# Leah_board.net
KiCad netlist of a schematic drawn in EAGLE
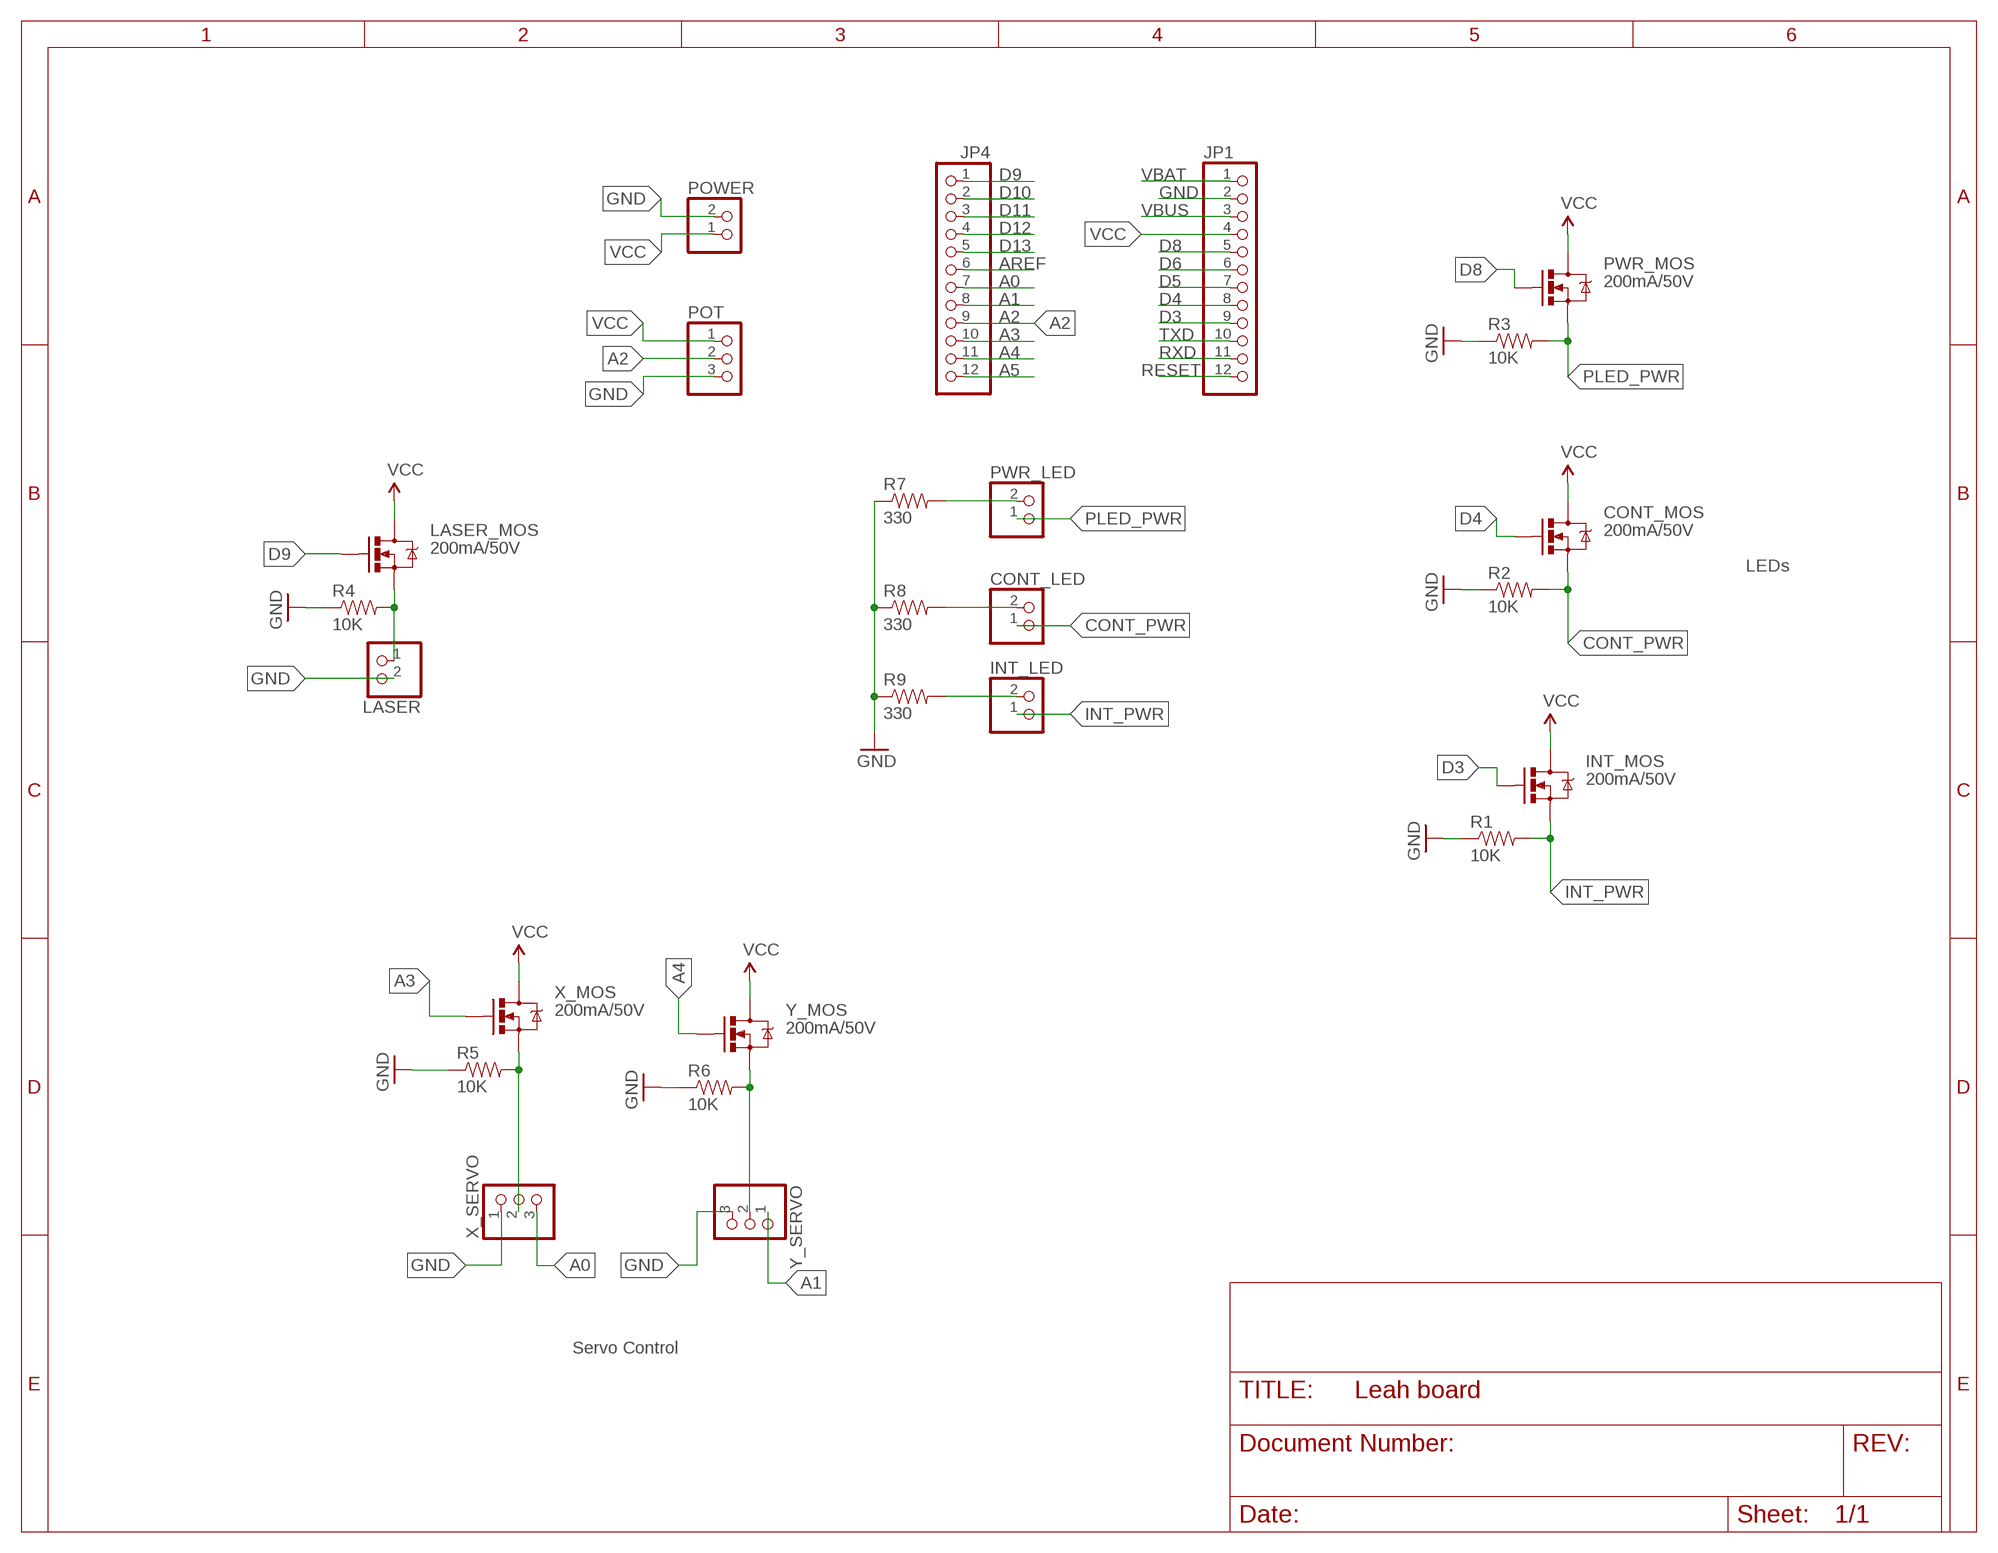
[diagram p0: schematic, sheet 1]

(export (version "E")
  (design (tool "Eeschema 10.0.6"))
  (components
    (comp (ref "CONT_LED")
      (value "JST_2PIN-SMT-RA")
      (footprint "eagle-import:JST-PH-2-SMT-RA")
      (libsource (lib "eagle-import") (part "JST_2PIN-SMT-RA"))
    )
    (comp (ref "CONT_MOS")
      (value "200mA/50V")
      (footprint "eagle-import:SOT23-3")
      (libsource (lib "eagle-import") (part "MOSFET-NCHANNELBSS138"))
    )
    (comp (ref "INT_LED")
      (value "JST_2PIN-SMT-RA")
      (footprint "eagle-import:JST-PH-2-SMT-RA")
      (libsource (lib "eagle-import") (part "JST_2PIN-SMT-RA"))
    )
    (comp (ref "INT_MOS")
      (value "200mA/50V")
      (footprint "eagle-import:SOT23-3")
      (libsource (lib "eagle-import") (part "MOSFET-NCHANNELBSS138"))
    )
    (comp (ref "JP1")
      (value "PINHD-1X12-CB")
      (footprint "eagle-import:1X12-CB")
      (libsource (lib "eagle-import") (part "PINHD-1X12-CB"))
    )
    (comp (ref "JP4")
      (value "PINHD-1X12-CB")
      (footprint "eagle-import:1X12-CB")
      (libsource (lib "eagle-import") (part "PINHD-1X12-CB"))
    )
    (comp (ref "LASER")
      (value "JST_2PIN-SMT-RA")
      (footprint "eagle-import:JST-PH-2-SMT-RA")
      (libsource (lib "eagle-import") (part "JST_2PIN-SMT-RA"))
    )
    (comp (ref "LASER_MOS")
      (value "200mA/50V")
      (footprint "eagle-import:SOT23-3")
      (libsource (lib "eagle-import") (part "MOSFET-NCHANNELBSS138"))
    )
    (comp (ref "POT")
      (value "JST_3PIN")
      (footprint "eagle-import:JSTPH3")
      (libsource (lib "eagle-import") (part "JST_3PIN"))
    )
    (comp (ref "POWER")
      (value "JST_2PIN-SMT-RA")
      (footprint "eagle-import:JST-PH-2-SMT-RA")
      (libsource (lib "eagle-import") (part "JST_2PIN-SMT-RA"))
    )
    (comp (ref "PWR_LED")
      (value "JST_2PIN-SMT-RA")
      (footprint "eagle-import:JST-PH-2-SMT-RA")
      (libsource (lib "eagle-import") (part "JST_2PIN-SMT-RA"))
    )
    (comp (ref "PWR_MOS")
      (value "200mA/50V")
      (footprint "eagle-import:SOT23-3")
      (libsource (lib "eagle-import") (part "MOSFET-NCHANNELBSS138"))
    )
    (comp (ref "R1")
      (value "10K")
      (footprint "eagle-import:0603-RES")
      (libsource (lib "eagle-import") (part "10KOHM-1/10W-1%(0603)0603"))
    )
    (comp (ref "R2")
      (value "10K")
      (footprint "eagle-import:0603-RES")
      (libsource (lib "eagle-import") (part "10KOHM-1/10W-1%(0603)0603"))
    )
    (comp (ref "R3")
      (value "10K")
      (footprint "eagle-import:0603-RES")
      (libsource (lib "eagle-import") (part "10KOHM-1/10W-1%(0603)0603"))
    )
    (comp (ref "R4")
      (value "10K")
      (footprint "eagle-import:0603-RES")
      (libsource (lib "eagle-import") (part "10KOHM-1/10W-1%(0603)0603"))
    )
    (comp (ref "R5")
      (value "10K")
      (footprint "eagle-import:0603-RES")
      (libsource (lib "eagle-import") (part "10KOHM-1/10W-1%(0603)0603"))
    )
    (comp (ref "R6")
      (value "10K")
      (footprint "eagle-import:0603-RES")
      (libsource (lib "eagle-import") (part "10KOHM-1/10W-1%(0603)0603"))
    )
    (comp (ref "R7")
      (value "330")
      (footprint "eagle-import:0603-RES")
      (libsource (lib "eagle-import") (part "3.3MOHM-1/10W-1%(0603)"))
    )
    (comp (ref "R8")
      (value "330")
      (footprint "eagle-import:0603-RES")
      (libsource (lib "eagle-import") (part "3.3MOHM-1/10W-1%(0603)"))
    )
    (comp (ref "R9")
      (value "330")
      (footprint "eagle-import:0603-RES")
      (libsource (lib "eagle-import") (part "3.3MOHM-1/10W-1%(0603)"))
    )
    (comp (ref "X_MOS")
      (value "200mA/50V")
      (footprint "eagle-import:SOT23-3")
      (libsource (lib "eagle-import") (part "MOSFET-NCHANNELBSS138"))
    )
    (comp (ref "X_SERVO")
      (value "PINHD-1X3")
      (footprint "eagle-import:1X03")
      (libsource (lib "eagle-import") (part "PINHD-1X3"))
    )
    (comp (ref "Y_MOS")
      (value "200mA/50V")
      (footprint "eagle-import:SOT23-3")
      (libsource (lib "eagle-import") (part "MOSFET-NCHANNELBSS138"))
    )
    (comp (ref "Y_SERVO")
      (value "PINHD-1X3")
      (footprint "eagle-import:1X03")
      (libsource (lib "eagle-import") (part "PINHD-1X3"))
    )
  )
  (nets
    (net (code "1") (name "/A5") (class "Default")
      (node (ref "JP4") (pin "12") (pinfunction "12_12") (pintype "passive"))
    )
    (net (code "2") (name "/AREF") (class "Default")
      (node (ref "JP4") (pin "6") (pinfunction "6_6") (pintype "passive"))
    )
    (net (code "3") (name "/D5") (class "Default")
      (node (ref "JP1") (pin "7") (pinfunction "7_7") (pintype "passive"))
    )
    (net (code "4") (name "/D6") (class "Default")
      (node (ref "JP1") (pin "6") (pinfunction "6_6") (pintype "passive"))
    )
    (net (code "5") (name "/D10") (class "Default")
      (node (ref "JP4") (pin "2") (pinfunction "2_2") (pintype "passive"))
    )
    (net (code "6") (name "/D11") (class "Default")
      (node (ref "JP4") (pin "3") (pinfunction "3_3") (pintype "passive"))
    )
    (net (code "7") (name "/D12") (class "Default")
      (node (ref "JP4") (pin "4") (pinfunction "4_4") (pintype "passive"))
    )
    (net (code "8") (name "/D13") (class "Default")
      (node (ref "JP4") (pin "5") (pinfunction "5_5") (pintype "passive"))
    )
    (net (code "9") (name "/RESET") (class "Default")
      (node (ref "JP1") (pin "12") (pinfunction "12_12") (pintype "passive"))
    )
    (net (code "10") (name "/RXD") (class "Default")
      (node (ref "JP1") (pin "11") (pinfunction "11_11") (pintype "passive"))
    )
    (net (code "11") (name "/TXD") (class "Default")
      (node (ref "JP1") (pin "10") (pinfunction "10_10") (pintype "passive"))
    )
    (net (code "12") (name "/VBAT") (class "Default")
      (node (ref "JP1") (pin "1") (pinfunction "1_1") (pintype "passive"))
    )
    (net (code "13") (name "/VBUS") (class "Default")
      (node (ref "JP1") (pin "3") (pinfunction "3_3") (pintype "passive"))
    )
    (net (code "14") (name "A0") (class "Default")
      (node (ref "JP4") (pin "7") (pinfunction "7_7") (pintype "passive"))
      (node (ref "X_SERVO") (pin "3") (pinfunction "3_3") (pintype "passive"))
    )
    (net (code "15") (name "A1") (class "Default")
      (node (ref "JP4") (pin "8") (pinfunction "8_8") (pintype "passive"))
      (node (ref "Y_SERVO") (pin "1") (pinfunction "1_1") (pintype "passive"))
    )
    (net (code "16") (name "A2") (class "Default")
      (node (ref "JP4") (pin "9") (pinfunction "9_9") (pintype "passive"))
      (node (ref "POT") (pin "2") (pinfunction "2_2") (pintype "passive"))
    )
    (net (code "17") (name "A3") (class "Default")
      (node (ref "JP4") (pin "10") (pinfunction "10_10") (pintype "passive"))
      (node (ref "X_MOS") (pin "1") (pinfunction "G_1") (pintype "passive"))
    )
    (net (code "18") (name "A4") (class "Default")
      (node (ref "JP4") (pin "11") (pinfunction "11_11") (pintype "passive"))
      (node (ref "Y_MOS") (pin "1") (pinfunction "G_1") (pintype "passive"))
    )
    (net (code "19") (name "CONT_PWR") (class "Default")
      (node (ref "CONT_LED") (pin "1") (pinfunction "2_1") (pintype "passive"))
      (node (ref "CONT_MOS") (pin "2") (pinfunction "S_2") (pintype "passive"))
      (node (ref "R2") (pin "2") (pinfunction "2_2") (pintype "passive"))
    )
    (net (code "20") (name "D3") (class "Default")
      (node (ref "INT_MOS") (pin "1") (pinfunction "G_1") (pintype "passive"))
      (node (ref "JP1") (pin "9") (pinfunction "9_9") (pintype "passive"))
    )
    (net (code "21") (name "D4") (class "Default")
      (node (ref "CONT_MOS") (pin "1") (pinfunction "G_1") (pintype "passive"))
      (node (ref "JP1") (pin "8") (pinfunction "8_8") (pintype "passive"))
    )
    (net (code "22") (name "D8") (class "Default")
      (node (ref "JP1") (pin "5") (pinfunction "5_5") (pintype "passive"))
      (node (ref "PWR_MOS") (pin "1") (pinfunction "G_1") (pintype "passive"))
    )
    (net (code "23") (name "D9") (class "Default")
      (node (ref "JP4") (pin "1") (pinfunction "1_1") (pintype "passive"))
      (node (ref "LASER_MOS") (pin "1") (pinfunction "G_1") (pintype "passive"))
    )
    (net (code "24") (name "GND") (class "Default")
      (node (ref "JP1") (pin "2") (pinfunction "2_2") (pintype "passive"))
      (node (ref "LASER") (pin "2") (pinfunction "1_2") (pintype "passive"))
      (node (ref "POT") (pin "3") (pinfunction "3_3") (pintype "passive"))
      (node (ref "POWER") (pin "2") (pinfunction "1_2") (pintype "passive"))
      (node (ref "R1") (pin "1") (pinfunction "1_1") (pintype "passive"))
      (node (ref "R2") (pin "1") (pinfunction "1_1") (pintype "passive"))
      (node (ref "R3") (pin "1") (pinfunction "1_1") (pintype "passive"))
      (node (ref "R4") (pin "1") (pinfunction "1_1") (pintype "passive"))
      (node (ref "R5") (pin "1") (pinfunction "1_1") (pintype "passive"))
      (node (ref "R6") (pin "1") (pinfunction "1_1") (pintype "passive"))
      (node (ref "R7") (pin "1") (pinfunction "1_1") (pintype "passive"))
      (node (ref "R8") (pin "1") (pinfunction "1_1") (pintype "passive"))
      (node (ref "R9") (pin "1") (pinfunction "1_1") (pintype "passive"))
      (node (ref "X_SERVO") (pin "1") (pinfunction "1_1") (pintype "passive"))
      (node (ref "Y_SERVO") (pin "3") (pinfunction "3_3") (pintype "passive"))
    )
    (net (code "25") (name "INT_PWR") (class "Default")
      (node (ref "INT_LED") (pin "1") (pinfunction "2_1") (pintype "passive"))
      (node (ref "INT_MOS") (pin "2") (pinfunction "S_2") (pintype "passive"))
      (node (ref "R1") (pin "2") (pinfunction "2_2") (pintype "passive"))
    )
    (net (code "26") (name "Net-(CONT_LED-1)") (class "Default")
      (node (ref "CONT_LED") (pin "2") (pinfunction "1_2") (pintype "passive"))
      (node (ref "R8") (pin "2") (pinfunction "2_2") (pintype "passive"))
    )
    (net (code "27") (name "Net-(INT_LED-1)") (class "Default")
      (node (ref "INT_LED") (pin "2") (pinfunction "1_2") (pintype "passive"))
      (node (ref "R9") (pin "2") (pinfunction "2_2") (pintype "passive"))
    )
    (net (code "28") (name "Net-(LASER-2)") (class "Default")
      (node (ref "LASER") (pin "1") (pinfunction "2_1") (pintype "passive"))
      (node (ref "LASER_MOS") (pin "2") (pinfunction "S_2") (pintype "passive"))
      (node (ref "R4") (pin "2") (pinfunction "2_2") (pintype "passive"))
    )
    (net (code "29") (name "Net-(PWR_LED-1)") (class "Default")
      (node (ref "PWR_LED") (pin "2") (pinfunction "1_2") (pintype "passive"))
      (node (ref "R7") (pin "2") (pinfunction "2_2") (pintype "passive"))
    )
    (net (code "30") (name "Net-(X_MOS-S)") (class "Default")
      (node (ref "R5") (pin "2") (pinfunction "2_2") (pintype "passive"))
      (node (ref "X_MOS") (pin "2") (pinfunction "S_2") (pintype "passive"))
      (node (ref "X_SERVO") (pin "2") (pinfunction "2_2") (pintype "passive"))
    )
    (net (code "31") (name "Net-(Y_MOS-S)") (class "Default")
      (node (ref "R6") (pin "2") (pinfunction "2_2") (pintype "passive"))
      (node (ref "Y_MOS") (pin "2") (pinfunction "S_2") (pintype "passive"))
      (node (ref "Y_SERVO") (pin "2") (pinfunction "2_2") (pintype "passive"))
    )
    (net (code "32") (name "PLED_PWR") (class "Default")
      (node (ref "PWR_LED") (pin "1") (pinfunction "2_1") (pintype "passive"))
      (node (ref "PWR_MOS") (pin "2") (pinfunction "S_2") (pintype "passive"))
      (node (ref "R3") (pin "2") (pinfunction "2_2") (pintype "passive"))
    )
    (net (code "33") (name "VCC") (class "Default")
      (node (ref "CONT_MOS") (pin "3") (pinfunction "D_3") (pintype "passive"))
      (node (ref "INT_MOS") (pin "3") (pinfunction "D_3") (pintype "passive"))
      (node (ref "JP1") (pin "4") (pinfunction "4_4") (pintype "passive"))
      (node (ref "LASER_MOS") (pin "3") (pinfunction "D_3") (pintype "passive"))
      (node (ref "POT") (pin "1") (pinfunction "1_1") (pintype "passive"))
      (node (ref "POWER") (pin "1") (pinfunction "2_1") (pintype "passive"))
      (node (ref "PWR_MOS") (pin "3") (pinfunction "D_3") (pintype "passive"))
      (node (ref "X_MOS") (pin "3") (pinfunction "D_3") (pintype "passive"))
      (node (ref "Y_MOS") (pin "3") (pinfunction "D_3") (pintype "passive"))
    )
  )
)
